# STM32L476_MCU.net
KiCad netlist of a schematic drawn in Altium Designer
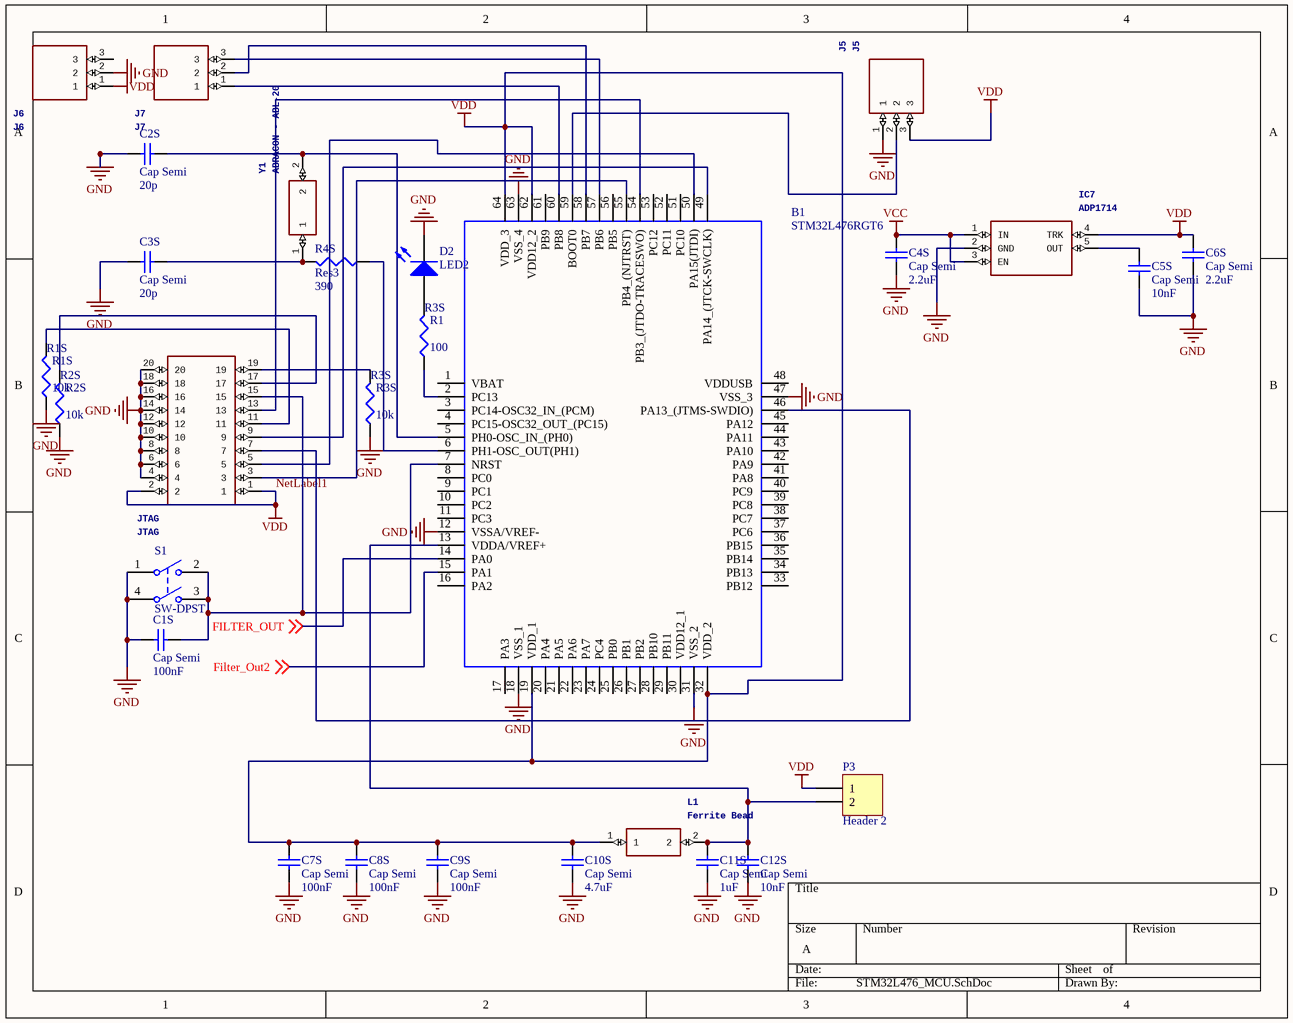
[diagram p0: STM32L476_MCU.SchDoc]

(export (version "E")
  (design (tool "Eeschema 10.0.6"))
  (components
    (comp (ref "B1")
      (value "STM32L476RGT6")
      (footprint "QFP50P1200X1200X160-64N")
      (fields (field (name "RS PART NUMBER") "1658235"))
      (libsource (lib "STM32L476RGT6") (part "STM32L476RGT6"))
    )
    (comp (ref "C1S")
      (value "Cap Semi")
      (footprint "1608[0603]")
      (description "Capacitor (Semiconductor SIM Model)")
      (fields (field (name "ALTIUM_VALUE") "100nF") (field (name "PUBLISHER") "Altium Limited"))
      (libsource (lib "Miscellaneous Devices") (part "Cap Semi"))
    )
    (comp (ref "C2S")
      (value "Cap Semi")
      (footprint "1608[0603]")
      (description "Capacitor (Semiconductor SIM Model)")
      (fields (field (name "ALTIUM_VALUE") "20p") (field (name "PUBLISHER") "Altium Limited"))
      (libsource (lib "Miscellaneous Devices") (part "Cap Semi"))
    )
    (comp (ref "C3S")
      (value "Cap Semi")
      (footprint "1608[0603]")
      (description "Capacitor (Semiconductor SIM Model)")
      (fields (field (name "ALTIUM_VALUE") "20p") (field (name "PUBLISHER") "Altium Limited"))
      (libsource (lib "Miscellaneous Devices") (part "Cap Semi"))
    )
    (comp (ref "C4S")
      (value "Cap Semi")
      (footprint "1608[0603]")
      (description "Capacitor (Semiconductor SIM Model)")
      (fields (field (name "ALTIUM_VALUE") "2.2uF") (field (name "PUBLISHER") "Altium Limited"))
      (libsource (lib "Miscellaneous Devices") (part "Cap Semi"))
    )
    (comp (ref "C5S")
      (value "Cap Semi")
      (footprint "1608[0603]")
      (description "Capacitor (Semiconductor SIM Model)")
      (fields (field (name "ALTIUM_VALUE") "10nF") (field (name "PUBLISHER") "Altium Limited"))
      (libsource (lib "Miscellaneous Devices") (part "Cap Semi"))
    )
    (comp (ref "C6S")
      (value "Cap Semi")
      (footprint "1608[0603]")
      (description "Capacitor (Semiconductor SIM Model)")
      (fields (field (name "ALTIUM_VALUE") "2.2uF") (field (name "PUBLISHER") "Altium Limited"))
      (libsource (lib "Miscellaneous Devices") (part "Cap Semi"))
    )
    (comp (ref "C7S")
      (value "Cap Semi")
      (footprint "1608[0603]")
      (description "Capacitor (Semiconductor SIM Model)")
      (fields (field (name "ALTIUM_VALUE") "100nF") (field (name "PUBLISHER") "Altium Limited"))
      (libsource (lib "Miscellaneous Devices") (part "Cap Semi"))
    )
    (comp (ref "C8S")
      (value "Cap Semi")
      (footprint "1608[0603]")
      (description "Capacitor (Semiconductor SIM Model)")
      (fields (field (name "ALTIUM_VALUE") "100nF") (field (name "PUBLISHER") "Altium Limited"))
      (libsource (lib "Miscellaneous Devices") (part "Cap Semi"))
    )
    (comp (ref "C9S")
      (value "Cap Semi")
      (footprint "1608[0603]")
      (description "Capacitor (Semiconductor SIM Model)")
      (fields (field (name "ALTIUM_VALUE") "100nF") (field (name "PUBLISHER") "Altium Limited"))
      (libsource (lib "Miscellaneous Devices") (part "Cap Semi"))
    )
    (comp (ref "C10S")
      (value "Cap Semi")
      (footprint "1608[0603]")
      (description "Capacitor (Semiconductor SIM Model)")
      (fields (field (name "ALTIUM_VALUE") "4.7uF") (field (name "PUBLISHER") "Altium Limited"))
      (libsource (lib "Miscellaneous Devices") (part "Cap Semi"))
    )
    (comp (ref "C11S")
      (value "Cap Semi")
      (footprint "1608[0603]")
      (description "Capacitor (Semiconductor SIM Model)")
      (fields (field (name "ALTIUM_VALUE") "1uF") (field (name "PUBLISHER") "Altium Limited"))
      (libsource (lib "Miscellaneous Devices") (part "Cap Semi"))
    )
    (comp (ref "C12S")
      (value "Cap Semi")
      (footprint "1608[0603]")
      (description "Capacitor (Semiconductor SIM Model)")
      (fields (field (name "ALTIUM_VALUE") "10nF") (field (name "PUBLISHER") "Altium Limited"))
      (libsource (lib "Miscellaneous Devices") (part "Cap Semi"))
    )
    (comp (ref "D2")
      (value "LED2")
      (footprint "1608[0603]")
      (description "Typical RED, GREEN, YELLOW, AMBER GaAs LED")
      (fields (field (name "PUBLISHER") "Altium Limited"))
      (libsource (lib "Miscellaneous Devices") (part "LED2"))
    )
    (comp (ref "IC7")
      (value "ADP1714")
      (footprint "SOT95P280X100-5N")
      (fields (field (name "MANUFACTURER_PART_NUMBER") "ADP1714AUJZ-3.3-R7"))
      (libsource (lib "ADP1714AUJZ-3") (part "ADP1714AUJZ-3.3-R7"))
    )
    (comp (ref "J5")
      (value "J5")
      (footprint "HDRV3W95P0X254_1X3_762X254X869")
      (fields
        (field (name "MANUFACTURER_PART_NUMBER") "61300311121")
        (field (name "RS_PART_NUMBER") "1725145")
      )
      (libsource (lib "61300311121") (part "61300311121"))
    )
    (comp (ref "J6")
      (value "J6")
      (footprint "HDRV3W95P0X254_1X3_762X254X869")
      (fields
        (field (name "MANUFACTURER_PART_NUMBER") "61300311121")
        (field (name "RS_PART_NUMBER") "1725145")
      )
      (libsource (lib "61300311121") (part "61300311121"))
    )
    (comp (ref "J7")
      (value "J7")
      (footprint "HDRV3W95P0X254_1X3_762X254X869")
      (fields
        (field (name "MANUFACTURER_PART_NUMBER") "61300311121")
        (field (name "RS_PART_NUMBER") "1725145")
      )
      (libsource (lib "61300311121") (part "61300311121"))
    )
    (comp (ref "JTAG")
      (value "JTAG")
      (footprint "SAMTEC_SSW-110-01-G")
      (fields
        (field (name "MANUFACTURER_PART_NUMBER") "SSW-110-01-G-D")
        (field (name "RS_PART_NUMBER") "7655727P")
      )
      (libsource (lib "SSW-110-01-G-D") (part "SSW-110-01-G-D"))
    )
    (comp (ref "L1")
      (value "Ferrite Bead")
      (footprint "BEADC1608X95N")
      (fields (field (name "MANUFACTURER_PART_NUMBER") "BK1608HS601-T"))
      (libsource (lib "BK1608HS601-T") (part "BK1608HS601-T"))
    )
    (comp (ref "P3")
      (value "Header 2")
      (footprint "HDR1X2")
      (description "Header, 2-Pin")
      (fields (field (name "PUBLISHER") "Altium Limited"))
      (libsource (lib "Miscellaneous Connectors") (part "Header 2"))
    )
    (comp (ref "R1")
      (value "R3S")
      (footprint "1608[0603]")
      (description "Resistor")
      (fields (field (name "ALTIUM_VALUE") "100") (field (name "PUBLISHER") "Altium Limited"))
      (libsource (lib "Miscellaneous Devices") (part "Res3"))
    )
    (comp (ref "R1S")
      (value "R1S")
      (footprint "1608[0603]")
      (description "Resistor")
      (fields (field (name "ALTIUM_VALUE") "10k") (field (name "PUBLISHER") "Altium Limited"))
      (libsource (lib "Miscellaneous Devices") (part "Res3"))
    )
    (comp (ref "R2S")
      (value "R2S")
      (footprint "1608[0603]")
      (description "Resistor")
      (fields (field (name "ALTIUM_VALUE") "10k") (field (name "PUBLISHER") "Altium Limited"))
      (libsource (lib "Miscellaneous Devices") (part "Res3"))
    )
    (comp (ref "R3S")
      (value "R3S")
      (footprint "1608[0603]")
      (description "Resistor")
      (fields (field (name "ALTIUM_VALUE") "10k") (field (name "PUBLISHER") "Altium Limited"))
      (libsource (lib "Miscellaneous Devices") (part "Res3"))
    )
    (comp (ref "R4S")
      (value "Res3")
      (footprint "1608[0603]")
      (description "Resistor")
      (fields (field (name "ALTIUM_VALUE") "390") (field (name "PUBLISHER") "Altium Limited"))
      (libsource (lib "Miscellaneous Devices") (part "Res3"))
    )
    (comp (ref "S1")
      (value "SW-DPST")
      (footprint "D6C10F1LFS")
      (description "Double-Pole, Single-Throw Switch")
      (fields (field (name "PUBLISHER") "Altium Limited"))
      (libsource (lib "Miscellaneous Devices") (part "SW-DPST"))
    )
    (comp (ref "Y1")
      (value "ABRACON - ABL-20")
      (footprint "HC/49US_(AT49)PTH")
      (fields
        (field (name "MANUFACTURER_PART_NUMBER") "ABL-20.000MHZ-B2")
        (field (name "RS_PART_NUMBER") "1710202")
      )
      (libsource (lib "ABL-20") (part "ABL-20.000MHZ-B2"))
    )
  )
  (nets
    (net (code "1") (name "FILTER_OUT") (class "Default")
      (node (ref "B1") (pin "14") (pinfunction "PA0_14") (pintype "passive"))
    )
    (net (code "2") (name "Filter_Out2") (class "Default")
      (node (ref "B1") (pin "15") (pinfunction "PA1_15") (pintype "passive"))
    )
    (net (code "3") (name "GND") (class "Default")
      (node (ref "B1") (pin "12") (pinfunction "VSSA/VREF-_12") (pintype "passive"))
      (node (ref "B1") (pin "18") (pinfunction "VSS_1_18") (pintype "passive"))
      (node (ref "B1") (pin "31") (pinfunction "VSS_2_31") (pintype "passive"))
      (node (ref "B1") (pin "47") (pinfunction "VSS_3_47") (pintype "passive"))
      (node (ref "B1") (pin "63") (pinfunction "VSS_4_63") (pintype "passive"))
      (node (ref "C10S") (pin "1") (pinfunction "1_1") (pintype "passive"))
      (node (ref "C11S") (pin "1") (pinfunction "1_1") (pintype "passive"))
      (node (ref "C12S") (pin "1") (pinfunction "1_1") (pintype "passive"))
      (node (ref "C1S") (pin "1") (pinfunction "1_1") (pintype "passive"))
      (node (ref "C2S") (pin "1") (pinfunction "1_1") (pintype "passive"))
      (node (ref "C3S") (pin "1") (pinfunction "1_1") (pintype "passive"))
      (node (ref "C4S") (pin "1") (pinfunction "1_1") (pintype "passive"))
      (node (ref "C5S") (pin "1") (pinfunction "1_1") (pintype "passive"))
      (node (ref "C6S") (pin "1") (pinfunction "1_1") (pintype "passive"))
      (node (ref "C7S") (pin "1") (pinfunction "1_1") (pintype "passive"))
      (node (ref "C8S") (pin "1") (pinfunction "1_1") (pintype "passive"))
      (node (ref "C9S") (pin "1") (pinfunction "1_1") (pintype "passive"))
      (node (ref "D2") (pin "2") (pinfunction "K_2") (pintype "passive"))
      (node (ref "IC7") (pin "2") (pinfunction "GND_2") (pintype "bidirectional"))
      (node (ref "J5") (pin "1") (pinfunction "1_1") (pintype "bidirectional"))
      (node (ref "J6") (pin "2") (pinfunction "2_2") (pintype "bidirectional"))
      (node (ref "JTAG") (pin "10") (pinfunction "10_10") (pintype "bidirectional"))
      (node (ref "JTAG") (pin "12") (pinfunction "12_12") (pintype "bidirectional"))
      (node (ref "JTAG") (pin "14") (pinfunction "14_14") (pintype "bidirectional"))
      (node (ref "JTAG") (pin "16") (pinfunction "16_16") (pintype "bidirectional"))
      (node (ref "JTAG") (pin "18") (pinfunction "18_18") (pintype "bidirectional"))
      (node (ref "JTAG") (pin "20") (pinfunction "20_20") (pintype "bidirectional"))
      (node (ref "JTAG") (pin "4") (pinfunction "4_4") (pintype "bidirectional"))
      (node (ref "JTAG") (pin "6") (pinfunction "6_6") (pintype "bidirectional"))
      (node (ref "JTAG") (pin "8") (pinfunction "8_8") (pintype "bidirectional"))
      (node (ref "R1S") (pin "2") (pinfunction "2_2") (pintype "passive"))
      (node (ref "R2S") (pin "2") (pinfunction "2_2") (pintype "passive"))
      (node (ref "R3S") (pin "2") (pinfunction "2_2") (pintype "passive"))
      (node (ref "S1") (pin "1") (pinfunction "COMMON1_1") (pintype "passive"))
      (node (ref "S1") (pin "4") (pinfunction "COMMON2_4") (pintype "passive"))
    )
    (net (code "4") (name "Net-(B1-BOOT0)") (class "Default")
      (node (ref "B1") (pin "59") (pinfunction "BOOT0_59") (pintype "passive"))
      (node (ref "J5") (pin "2") (pinfunction "2_2") (pintype "bidirectional"))
    )
    (net (code "5") (name "Net-(B1-NRST)") (class "Default")
      (node (ref "B1") (pin "7") (pinfunction "NRST_7") (pintype "passive"))
      (node (ref "C1S") (pin "2") (pinfunction "2_2") (pintype "passive"))
      (node (ref "JTAG") (pin "15") (pinfunction "15_15") (pintype "bidirectional"))
      (node (ref "S1") (pin "2") (pinfunction "NO1_2") (pintype "passive"))
      (node (ref "S1") (pin "3") (pinfunction "NO2_3") (pintype "passive"))
    )
    (net (code "6") (name "Net-(B1-PA13_(JTMS-SWDIO))") (class "Default")
      (node (ref "B1") (pin "46") (pinfunction "PA13_(JTMS-SWDIO)_46") (pintype "passive"))
      (node (ref "JTAG") (pin "7") (pinfunction "7_7") (pintype "bidirectional"))
    )
    (net (code "7") (name "Net-(B1-PA14_(JTCK-SWCLK))") (class "Default")
      (node (ref "B1") (pin "49") (pinfunction "PA14_(JTCK-SWCLK)_49") (pintype "passive"))
      (node (ref "JTAG") (pin "9") (pinfunction "9_9") (pintype "bidirectional"))
    )
    (net (code "8") (name "Net-(B1-PA15(JTDI))") (class "Default")
      (node (ref "B1") (pin "50") (pinfunction "PA15(JTDI)_50") (pintype "passive"))
      (node (ref "JTAG") (pin "5") (pinfunction "5_5") (pintype "bidirectional"))
    )
    (net (code "9") (name "Net-(B1-PB3_(JTDO-TRACESWO))") (class "Default")
      (node (ref "B1") (pin "54") (pinfunction "PB3_(JTDO-TRACESWO)_54") (pintype "passive"))
      (node (ref "JTAG") (pin "13") (pinfunction "13_13") (pintype "bidirectional"))
    )
    (net (code "10") (name "Net-(B1-PB4_(NJTRST))") (class "Default")
      (node (ref "B1") (pin "55") (pinfunction "PB4_(NJTRST)_55") (pintype "passive"))
      (node (ref "JTAG") (pin "3") (pinfunction "3_3") (pintype "bidirectional"))
    )
    (net (code "11") (name "Net-(B1-PB6)") (class "Default")
      (node (ref "B1") (pin "57") (pinfunction "PB6_57") (pintype "passive"))
      (node (ref "J7") (pin "3") (pinfunction "3_3") (pintype "bidirectional"))
    )
    (net (code "12") (name "Net-(B1-PB7)") (class "Default")
      (node (ref "B1") (pin "58") (pinfunction "PB7_58") (pintype "passive"))
      (node (ref "J7") (pin "2") (pinfunction "2_2") (pintype "bidirectional"))
    )
    (net (code "13") (name "Net-(B1-PB8)") (class "Default")
      (node (ref "B1") (pin "60") (pinfunction "PB8_60") (pintype "passive"))
      (node (ref "J7") (pin "1") (pinfunction "1_1") (pintype "bidirectional"))
    )
    (net (code "14") (name "Net-(B1-PC13)") (class "Default")
      (node (ref "B1") (pin "2") (pinfunction "PC13_2") (pintype "passive"))
      (node (ref "R1") (pin "2") (pinfunction "2_2") (pintype "passive"))
    )
    (net (code "15") (name "Net-(B1-PH0-OSC_IN_(PH0))") (class "Default")
      (node (ref "B1") (pin "5") (pinfunction "PH0-OSC_IN_(PH0)_5") (pintype "passive"))
      (node (ref "C2S") (pin "2") (pinfunction "2_2") (pintype "passive"))
      (node (ref "Y1") (pin "2") (pinfunction "2_2") (pintype "bidirectional"))
    )
    (net (code "16") (name "Net-(B1-PH1-OSC_OUT(PH1))") (class "Default")
      (node (ref "B1") (pin "6") (pinfunction "PH1-OSC_OUT(PH1)_6") (pintype "passive"))
      (node (ref "R4S") (pin "2") (pinfunction "2_2") (pintype "passive"))
    )
    (net (code "17") (name "Net-(B1-VDDA{slash}VREF+)") (class "Default")
      (node (ref "B1") (pin "13") (pinfunction "VDDA/VREF+_13") (pintype "passive"))
      (node (ref "C11S") (pin "2") (pinfunction "2_2") (pintype "passive"))
      (node (ref "C12S") (pin "2") (pinfunction "2_2") (pintype "passive"))
      (node (ref "L1") (pin "2") (pinfunction "2_2") (pintype "bidirectional"))
      (node (ref "P3") (pin "2") (pinfunction "2_2") (pintype "passive"))
    )
    (net (code "18") (name "Net-(C3S-Pad2)") (class "Default")
      (node (ref "C3S") (pin "2") (pinfunction "2_2") (pintype "passive"))
      (node (ref "R4S") (pin "1") (pinfunction "1_1") (pintype "passive"))
      (node (ref "Y1") (pin "1") (pinfunction "1_1") (pintype "bidirectional"))
    )
    (net (code "19") (name "Net-(D2-A)") (class "Default")
      (node (ref "D2") (pin "1") (pinfunction "A_1") (pintype "passive"))
      (node (ref "R1") (pin "1") (pinfunction "1_1") (pintype "passive"))
    )
    (net (code "20") (name "Net-(IC7-OUT)") (class "Default")
      (node (ref "C5S") (pin "2") (pinfunction "2_2") (pintype "passive"))
      (node (ref "IC7") (pin "5") (pinfunction "OUT_5") (pintype "bidirectional"))
    )
    (net (code "21") (name "Net-(JTAG-Pad11)") (class "Default")
      (node (ref "JTAG") (pin "11") (pinfunction "11_11") (pintype "bidirectional"))
      (node (ref "R1S") (pin "1") (pinfunction "1_1") (pintype "passive"))
    )
    (net (code "22") (name "Net-(JTAG-Pad17)") (class "Default")
      (node (ref "JTAG") (pin "17") (pinfunction "17_17") (pintype "bidirectional"))
      (node (ref "R2S") (pin "1") (pinfunction "1_1") (pintype "passive"))
    )
    (net (code "23") (name "Net-(JTAG-Pad19)") (class "Default")
      (node (ref "JTAG") (pin "19") (pinfunction "19_19") (pintype "bidirectional"))
      (node (ref "R3S") (pin "1") (pinfunction "1_1") (pintype "passive"))
    )
    (net (code "24") (name "VCC") (class "Default")
      (node (ref "C4S") (pin "2") (pinfunction "2_2") (pintype "passive"))
      (node (ref "IC7") (pin "1") (pinfunction "IN_1") (pintype "bidirectional"))
      (node (ref "IC7") (pin "3") (pinfunction "EN_3") (pintype "bidirectional"))
    )
    (net (code "25") (name "VDD") (class "Default")
      (node (ref "B1") (pin "19") (pinfunction "VDD_1_19") (pintype "passive"))
      (node (ref "B1") (pin "32") (pinfunction "VDD_2_32") (pintype "passive"))
      (node (ref "B1") (pin "62") (pinfunction "VDD12_2_62") (pintype "passive"))
      (node (ref "B1") (pin "64") (pinfunction "VDD_3_64") (pintype "passive"))
      (node (ref "C10S") (pin "2") (pinfunction "2_2") (pintype "passive"))
      (node (ref "C6S") (pin "2") (pinfunction "2_2") (pintype "passive"))
      (node (ref "C7S") (pin "2") (pinfunction "2_2") (pintype "passive"))
      (node (ref "C8S") (pin "2") (pinfunction "2_2") (pintype "passive"))
      (node (ref "C9S") (pin "2") (pinfunction "2_2") (pintype "passive"))
      (node (ref "IC7") (pin "4") (pinfunction "TRK_4") (pintype "bidirectional"))
      (node (ref "J5") (pin "3") (pinfunction "3_3") (pintype "bidirectional"))
      (node (ref "J6") (pin "1") (pinfunction "1_1") (pintype "bidirectional"))
      (node (ref "JTAG") (pin "1") (pinfunction "1_1") (pintype "bidirectional"))
      (node (ref "JTAG") (pin "2") (pinfunction "2_2") (pintype "bidirectional"))
      (node (ref "L1") (pin "1") (pinfunction "1_1") (pintype "bidirectional"))
      (node (ref "P3") (pin "1") (pinfunction "1_1") (pintype "passive"))
    )
    (net (code "26") (name "unconnected-(B1-PA2-Pad16)") (class "Default")
      (node (ref "B1") (pin "16") (pinfunction "PA2_16") (pintype "passive"))
    )
    (net (code "27") (name "unconnected-(B1-PA3-Pad17)") (class "Default")
      (node (ref "B1") (pin "17") (pinfunction "PA3_17") (pintype "passive"))
    )
    (net (code "28") (name "unconnected-(B1-PA4-Pad20)") (class "Default")
      (node (ref "B1") (pin "20") (pinfunction "PA4_20") (pintype "passive"))
    )
    (net (code "29") (name "unconnected-(B1-PA5-Pad21)") (class "Default")
      (node (ref "B1") (pin "21") (pinfunction "PA5_21") (pintype "passive"))
    )
    (net (code "30") (name "unconnected-(B1-PA6-Pad22)") (class "Default")
      (node (ref "B1") (pin "22") (pinfunction "PA6_22") (pintype "passive"))
    )
    (net (code "31") (name "unconnected-(B1-PA7-Pad23)") (class "Default")
      (node (ref "B1") (pin "23") (pinfunction "PA7_23") (pintype "passive"))
    )
    (net (code "32") (name "unconnected-(B1-PA8-Pad41)") (class "Default")
      (node (ref "B1") (pin "41") (pinfunction "PA8_41") (pintype "passive"))
    )
    (net (code "33") (name "unconnected-(B1-PA9-Pad42)") (class "Default")
      (node (ref "B1") (pin "42") (pinfunction "PA9_42") (pintype "passive"))
    )
    (net (code "34") (name "unconnected-(B1-PA10-Pad43)") (class "Default")
      (node (ref "B1") (pin "43") (pinfunction "PA10_43") (pintype "passive"))
    )
    (net (code "35") (name "unconnected-(B1-PA11-Pad44)") (class "Default")
      (node (ref "B1") (pin "44") (pinfunction "PA11_44") (pintype "passive"))
    )
    (net (code "36") (name "unconnected-(B1-PA12-Pad45)") (class "Default")
      (node (ref "B1") (pin "45") (pinfunction "PA12_45") (pintype "passive"))
    )
    (net (code "37") (name "unconnected-(B1-PB0-Pad25)") (class "Default")
      (node (ref "B1") (pin "25") (pinfunction "PB0_25") (pintype "passive"))
    )
    (net (code "38") (name "unconnected-(B1-PB1-Pad26)") (class "Default")
      (node (ref "B1") (pin "26") (pinfunction "PB1_26") (pintype "passive"))
    )
    (net (code "39") (name "unconnected-(B1-PB2-Pad27)") (class "Default")
      (node (ref "B1") (pin "27") (pinfunction "PB2_27") (pintype "passive"))
    )
    (net (code "40") (name "unconnected-(B1-PB5-Pad56)") (class "Default")
      (node (ref "B1") (pin "56") (pinfunction "PB5_56") (pintype "passive"))
    )
    (net (code "41") (name "unconnected-(B1-PB9-Pad61)") (class "Default")
      (node (ref "B1") (pin "61") (pinfunction "PB9_61") (pintype "passive"))
    )
    (net (code "42") (name "unconnected-(B1-PB10-Pad28)") (class "Default")
      (node (ref "B1") (pin "28") (pinfunction "PB10_28") (pintype "passive"))
    )
    (net (code "43") (name "unconnected-(B1-PB11-Pad29)") (class "Default")
      (node (ref "B1") (pin "29") (pinfunction "PB11_29") (pintype "passive"))
    )
    (net (code "44") (name "unconnected-(B1-PB12-Pad33)") (class "Default")
      (node (ref "B1") (pin "33") (pinfunction "PB12_33") (pintype "passive"))
    )
    (net (code "45") (name "unconnected-(B1-PB13-Pad34)") (class "Default")
      (node (ref "B1") (pin "34") (pinfunction "PB13_34") (pintype "passive"))
    )
    (net (code "46") (name "unconnected-(B1-PB14-Pad35)") (class "Default")
      (node (ref "B1") (pin "35") (pinfunction "PB14_35") (pintype "passive"))
    )
    (net (code "47") (name "unconnected-(B1-PB15-Pad36)") (class "Default")
      (node (ref "B1") (pin "36") (pinfunction "PB15_36") (pintype "passive"))
    )
    (net (code "48") (name "unconnected-(B1-PC0-Pad8)") (class "Default")
      (node (ref "B1") (pin "8") (pinfunction "PC0_8") (pintype "passive"))
    )
    (net (code "49") (name "unconnected-(B1-PC1-Pad9)") (class "Default")
      (node (ref "B1") (pin "9") (pinfunction "PC1_9") (pintype "passive"))
    )
    (net (code "50") (name "unconnected-(B1-PC2-Pad10)") (class "Default")
      (node (ref "B1") (pin "10") (pinfunction "PC2_10") (pintype "passive"))
    )
    (net (code "51") (name "unconnected-(B1-PC3-Pad11)") (class "Default")
      (node (ref "B1") (pin "11") (pinfunction "PC3_11") (pintype "passive"))
    )
    (net (code "52") (name "unconnected-(B1-PC4-Pad24)") (class "Default")
      (node (ref "B1") (pin "24") (pinfunction "PC4_24") (pintype "passive"))
    )
    (net (code "53") (name "unconnected-(B1-PC6-Pad37)") (class "Default")
      (node (ref "B1") (pin "37") (pinfunction "PC6_37") (pintype "passive"))
    )
    (net (code "54") (name "unconnected-(B1-PC7-Pad38)") (class "Default")
      (node (ref "B1") (pin "38") (pinfunction "PC7_38") (pintype "passive"))
    )
    (net (code "55") (name "unconnected-(B1-PC8-Pad39)") (class "Default")
      (node (ref "B1") (pin "39") (pinfunction "PC8_39") (pintype "passive"))
    )
    (net (code "56") (name "unconnected-(B1-PC9-Pad40)") (class "Default")
      (node (ref "B1") (pin "40") (pinfunction "PC9_40") (pintype "passive"))
    )
    (net (code "57") (name "unconnected-(B1-PC10-Pad51)") (class "Default")
      (node (ref "B1") (pin "51") (pinfunction "PC10_51") (pintype "passive"))
    )
    (net (code "58") (name "unconnected-(B1-PC11-Pad52)") (class "Default")
      (node (ref "B1") (pin "52") (pinfunction "PC11_52") (pintype "passive"))
    )
    (net (code "59") (name "unconnected-(B1-PC12-Pad53)") (class "Default")
      (node (ref "B1") (pin "53") (pinfunction "PC12_53") (pintype "passive"))
    )
    (net (code "60") (name "unconnected-(B1-PC14-OSC32_IN_(PCM)-Pad3)") (class "Default")
      (node (ref "B1") (pin "3") (pinfunction "PC14-OSC32_IN_(PCM)_3") (pintype "passive"))
    )
    (net (code "61") (name "unconnected-(B1-PC15-OSC32_OUT_(PC15)-Pad4)") (class "Default")
      (node (ref "B1") (pin "4") (pinfunction "PC15-OSC32_OUT_(PC15)_4") (pintype "passive"))
    )
    (net (code "62") (name "unconnected-(B1-VBAT-Pad1)") (class "Default")
      (node (ref "B1") (pin "1") (pinfunction "VBAT_1") (pintype "passive"))
    )
    (net (code "63") (name "unconnected-(B1-VDD12_1-Pad30)") (class "Default")
      (node (ref "B1") (pin "30") (pinfunction "VDD12_1_30") (pintype "passive"))
    )
    (net (code "64") (name "unconnected-(B1-VDDUSB-Pad48)") (class "Default")
      (node (ref "B1") (pin "48") (pinfunction "VDDUSB_48") (pintype "passive"))
    )
    (net (code "65") (name "unconnected-(J6-Pad3)") (class "Default")
      (node (ref "J6") (pin "3") (pinfunction "3_3") (pintype "bidirectional"))
    )
  )
)
